# Filter_Capacitors_-_Port_A.net
KiCad netlist of a schematic drawn in Altium Designer
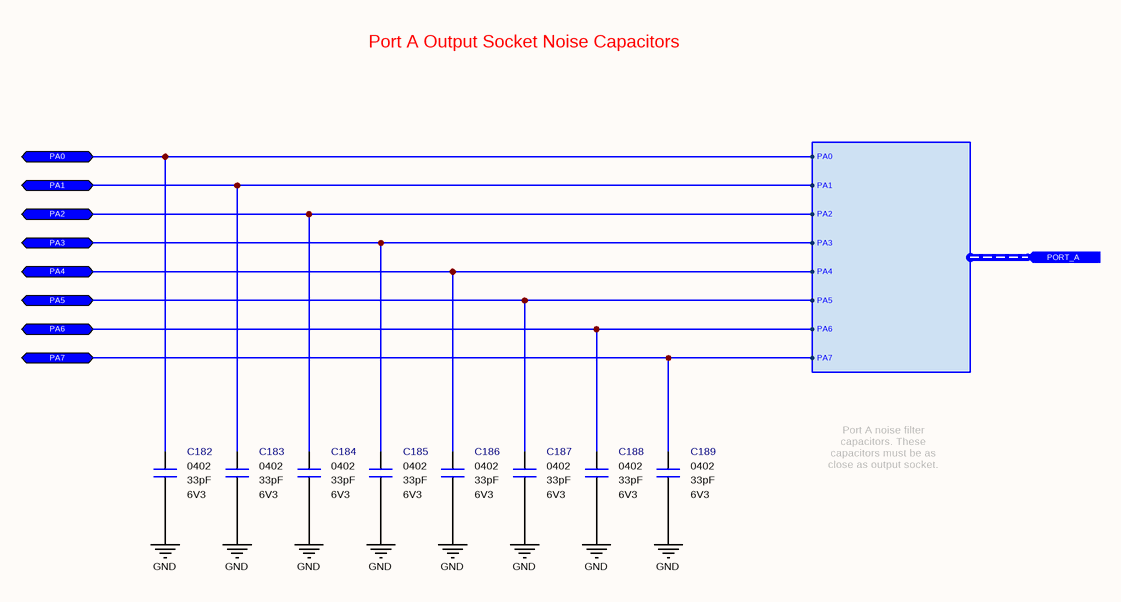
[diagram p0: Filter Capacitors - Port A.SchDoc]

(export (version "E")
  (design (tool "Eeschema 10.0.6"))
  (components
    (comp (ref "C182")
      (value "33pF")
      (footprint "CAPACITOR_0402")
      (description "Capacitor - 33pF [0402] (Ceramic)")
      (fields
        (field (name "TOLERANCE") "10%")
        (field (name "CASE") "0402")
        (field (name "VOLTAGE") "6V3")
        (field (name "MANUFACTURER PART NUMBER") "C0402C330J9RACAUTO")
      )
      (libsource (lib "Ovoo_Library") (part "Capacitor - 33pF [0402-6V3]"))
    )
    (comp (ref "C183")
      (value "33pF")
      (footprint "CAPACITOR_0402")
      (description "Capacitor - 33pF [0402] (Ceramic)")
      (fields
        (field (name "TOLERANCE") "10%")
        (field (name "CASE") "0402")
        (field (name "VOLTAGE") "6V3")
        (field (name "MANUFACTURER PART NUMBER") "C0402C330J9RACAUTO")
      )
      (libsource (lib "Ovoo_Library") (part "Capacitor - 33pF [0402-6V3]"))
    )
    (comp (ref "C184")
      (value "33pF")
      (footprint "CAPACITOR_0402")
      (description "Capacitor - 33pF [0402] (Ceramic)")
      (fields
        (field (name "TOLERANCE") "10%")
        (field (name "CASE") "0402")
        (field (name "VOLTAGE") "6V3")
        (field (name "MANUFACTURER PART NUMBER") "C0402C330J9RACAUTO")
      )
      (libsource (lib "Ovoo_Library") (part "Capacitor - 33pF [0402-6V3]"))
    )
    (comp (ref "C185")
      (value "33pF")
      (footprint "CAPACITOR_0402")
      (description "Capacitor - 33pF [0402] (Ceramic)")
      (fields
        (field (name "TOLERANCE") "10%")
        (field (name "CASE") "0402")
        (field (name "VOLTAGE") "6V3")
        (field (name "MANUFACTURER PART NUMBER") "C0402C330J9RACAUTO")
      )
      (libsource (lib "Ovoo_Library") (part "Capacitor - 33pF [0402-6V3]"))
    )
    (comp (ref "C186")
      (value "33pF")
      (footprint "CAPACITOR_0402")
      (description "Capacitor - 33pF [0402] (Ceramic)")
      (fields
        (field (name "TOLERANCE") "10%")
        (field (name "CASE") "0402")
        (field (name "VOLTAGE") "6V3")
        (field (name "MANUFACTURER PART NUMBER") "C0402C330J9RACAUTO")
      )
      (libsource (lib "Ovoo_Library") (part "Capacitor - 33pF [0402-6V3]"))
    )
    (comp (ref "C187")
      (value "33pF")
      (footprint "CAPACITOR_0402")
      (description "Capacitor - 33pF [0402] (Ceramic)")
      (fields
        (field (name "TOLERANCE") "10%")
        (field (name "CASE") "0402")
        (field (name "VOLTAGE") "6V3")
        (field (name "MANUFACTURER PART NUMBER") "C0402C330J9RACAUTO")
      )
      (libsource (lib "Ovoo_Library") (part "Capacitor - 33pF [0402-6V3]"))
    )
    (comp (ref "C188")
      (value "33pF")
      (footprint "CAPACITOR_0402")
      (description "Capacitor - 33pF [0402] (Ceramic)")
      (fields
        (field (name "TOLERANCE") "10%")
        (field (name "CASE") "0402")
        (field (name "VOLTAGE") "6V3")
        (field (name "MANUFACTURER PART NUMBER") "C0402C330J9RACAUTO")
      )
      (libsource (lib "Ovoo_Library") (part "Capacitor - 33pF [0402-6V3]"))
    )
    (comp (ref "C189")
      (value "33pF")
      (footprint "CAPACITOR_0402")
      (description "Capacitor - 33pF [0402] (Ceramic)")
      (fields
        (field (name "TOLERANCE") "10%")
        (field (name "CASE") "0402")
        (field (name "VOLTAGE") "6V3")
        (field (name "MANUFACTURER PART NUMBER") "C0402C330J9RACAUTO")
      )
      (libsource (lib "Ovoo_Library") (part "Capacitor - 33pF [0402-6V3]"))
    )
  )
  (nets
    (net (code "2") (name "/PA0") (class "Default")
      (node (ref "C182") (pin "2") (pinfunction "2_2") (pintype "passive"))
    )
    (net (code "3") (name "/PA1") (class "Default")
      (node (ref "C183") (pin "2") (pinfunction "2_2") (pintype "passive"))
    )
    (net (code "4") (name "/PA2") (class "Default")
      (node (ref "C184") (pin "2") (pinfunction "2_2") (pintype "passive"))
    )
    (net (code "5") (name "/PA3") (class "Default")
      (node (ref "C185") (pin "2") (pinfunction "2_2") (pintype "passive"))
    )
    (net (code "6") (name "/PA4") (class "Default")
      (node (ref "C186") (pin "2") (pinfunction "2_2") (pintype "passive"))
    )
    (net (code "7") (name "/PA5") (class "Default")
      (node (ref "C187") (pin "2") (pinfunction "2_2") (pintype "passive"))
    )
    (net (code "8") (name "/PA6") (class "Default")
      (node (ref "C188") (pin "2") (pinfunction "2_2") (pintype "passive"))
    )
    (net (code "9") (name "/PA7") (class "Default")
      (node (ref "C189") (pin "2") (pinfunction "2_2") (pintype "passive"))
    )
    (net (code "11") (name "GND") (class "Default")
      (node (ref "C182") (pin "1") (pinfunction "1_1") (pintype "passive"))
      (node (ref "C183") (pin "1") (pinfunction "1_1") (pintype "passive"))
      (node (ref "C184") (pin "1") (pinfunction "1_1") (pintype "passive"))
      (node (ref "C185") (pin "1") (pinfunction "1_1") (pintype "passive"))
      (node (ref "C186") (pin "1") (pinfunction "1_1") (pintype "passive"))
      (node (ref "C187") (pin "1") (pinfunction "1_1") (pintype "passive"))
      (node (ref "C188") (pin "1") (pinfunction "1_1") (pintype "passive"))
      (node (ref "C189") (pin "1") (pinfunction "1_1") (pintype "passive"))
    )
  )
)
